# PMW_Circuit.net
KiCad netlist of a schematic drawn in EAGLE
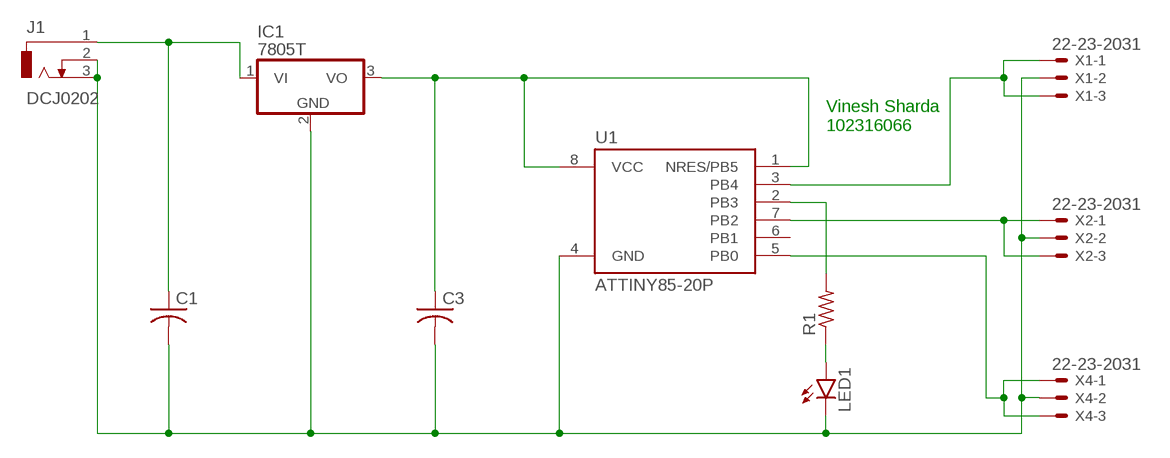
[diagram p0: schematic, sheet 1]

(export (version "E")
  (design (tool "Eeschema 10.0.6"))
  (components
    (comp (ref "C1")
      (value "C-US025-024X044")
      (footprint "eagle-import:C025-024X044")
      (libsource (lib "eagle-import") (part "C-US025-024X044"))
    )
    (comp (ref "C3")
      (value "C-US025-024X044")
      (footprint "eagle-import:C025-024X044")
      (libsource (lib "eagle-import") (part "C-US025-024X044"))
    )
    (comp (ref "IC1")
      (value "7805T")
      (footprint "eagle-import:TO220H")
      (libsource (lib "eagle-import") (part "78T05"))
    )
    (comp (ref "J1")
      (value "DCJ0202")
      (footprint "eagle-import:DCJ0202")
      (libsource (lib "eagle-import") (part "DCJ0202"))
    )
    (comp (ref "LED1")
      (value "LED3MM")
      (footprint "eagle-import:LED3MM")
      (libsource (lib "eagle-import") (part "LED3MM"))
    )
    (comp (ref "R1")
      (value "R-US_0204/5")
      (footprint "eagle-import:0204_5")
      (libsource (lib "eagle-import") (part "R-US_0204/5"))
    )
    (comp (ref "U1")
      (value "ATTINY85-20P")
      (footprint "eagle-import:PDIP08_300MIL")
      (libsource (lib "eagle-import") (part "ATTINY85P-20"))
    )
    (comp (ref "X1")
      (value "22-23-2031")
      (footprint "eagle-import:22-23-2031")
      (fields (field (name "MF") "MOLEX"))
      (libsource (lib "eagle-import") (part "22-23-2031"))
    )
    (comp (ref "X2")
      (value "22-23-2031")
      (footprint "eagle-import:22-23-2031")
      (fields (field (name "MF") "MOLEX"))
      (libsource (lib "eagle-import") (part "22-23-2031"))
    )
    (comp (ref "X4")
      (value "22-23-2031")
      (footprint "eagle-import:22-23-2031")
      (fields (field (name "MF") "MOLEX"))
      (libsource (lib "eagle-import") (part "22-23-2031"))
    )
  )
  (nets
    (net (code "1") (name "Net-(IC1-GND)") (class "Default")
      (node (ref "C1") (pin "2") (pinfunction "2_2") (pintype "passive"))
      (node (ref "C3") (pin "2") (pinfunction "2_2") (pintype "passive"))
      (node (ref "IC1") (pin "2") (pinfunction "GND_2") (pintype "passive"))
      (node (ref "J1") (pin "2") (pinfunction "2_2") (pintype "passive"))
      (node (ref "J1") (pin "3") (pinfunction "3_3") (pintype "passive"))
      (node (ref "LED1") (pin "K") (pinfunction "C_K") (pintype "passive"))
      (node (ref "U1") (pin "4") (pinfunction "GND_4") (pintype "power_in"))
      (node (ref "X1") (pin "2") (pinfunction "S_2") (pintype "passive"))
      (node (ref "X2") (pin "2") (pinfunction "S_2") (pintype "passive"))
      (node (ref "X4") (pin "2") (pinfunction "S_2") (pintype "passive"))
    )
    (net (code "2") (name "Net-(IC1-VI)") (class "Default")
      (node (ref "C1") (pin "1") (pinfunction "1_1") (pintype "passive"))
      (node (ref "IC1") (pin "1") (pinfunction "VI_1") (pintype "input"))
      (node (ref "J1") (pin "1") (pinfunction "1_1") (pintype "passive"))
    )
    (net (code "3") (name "Net-(IC1-VO)") (class "Default")
      (node (ref "C3") (pin "1") (pinfunction "1_1") (pintype "passive"))
      (node (ref "IC1") (pin "3") (pinfunction "VO_3") (pintype "passive"))
      (node (ref "U1") (pin "1") (pinfunction "NRES/PB5_1") (pintype "bidirectional"))
      (node (ref "U1") (pin "8") (pinfunction "VCC_8") (pintype "power_in"))
    )
    (net (code "4") (name "Net-(LED1-PadA)") (class "Default")
      (node (ref "LED1") (pin "A") (pinfunction "A_A") (pintype "passive"))
      (node (ref "R1") (pin "1") (pinfunction "1_1") (pintype "passive"))
    )
    (net (code "5") (name "Net-(U1-PB0)") (class "Default")
      (node (ref "U1") (pin "5") (pinfunction "PB0_5") (pintype "bidirectional"))
      (node (ref "X4") (pin "1") (pinfunction "S_1") (pintype "passive"))
      (node (ref "X4") (pin "3") (pinfunction "S_3") (pintype "passive"))
    )
    (net (code "6") (name "Net-(U1-PB2)") (class "Default")
      (node (ref "U1") (pin "7") (pinfunction "PB2_7") (pintype "bidirectional"))
      (node (ref "X2") (pin "1") (pinfunction "S_1") (pintype "passive"))
      (node (ref "X2") (pin "3") (pinfunction "S_3") (pintype "passive"))
    )
    (net (code "7") (name "Net-(U1-PB3)") (class "Default")
      (node (ref "R1") (pin "2") (pinfunction "2_2") (pintype "passive"))
      (node (ref "U1") (pin "2") (pinfunction "PB3_2") (pintype "bidirectional"))
    )
    (net (code "8") (name "Net-(U1-PB4)") (class "Default")
      (node (ref "U1") (pin "3") (pinfunction "PB4_3") (pintype "bidirectional"))
      (node (ref "X1") (pin "1") (pinfunction "S_1") (pintype "passive"))
      (node (ref "X1") (pin "3") (pinfunction "S_3") (pintype "passive"))
    )
    (net (code "9") (name "unconnected-(U1-PB1-Pad6)") (class "Default")
      (node (ref "U1") (pin "6") (pinfunction "PB1_6") (pintype "bidirectional"))
    )
  )
)
